# Encoder.net
KiCad netlist of a schematic drawn in Altium Designer
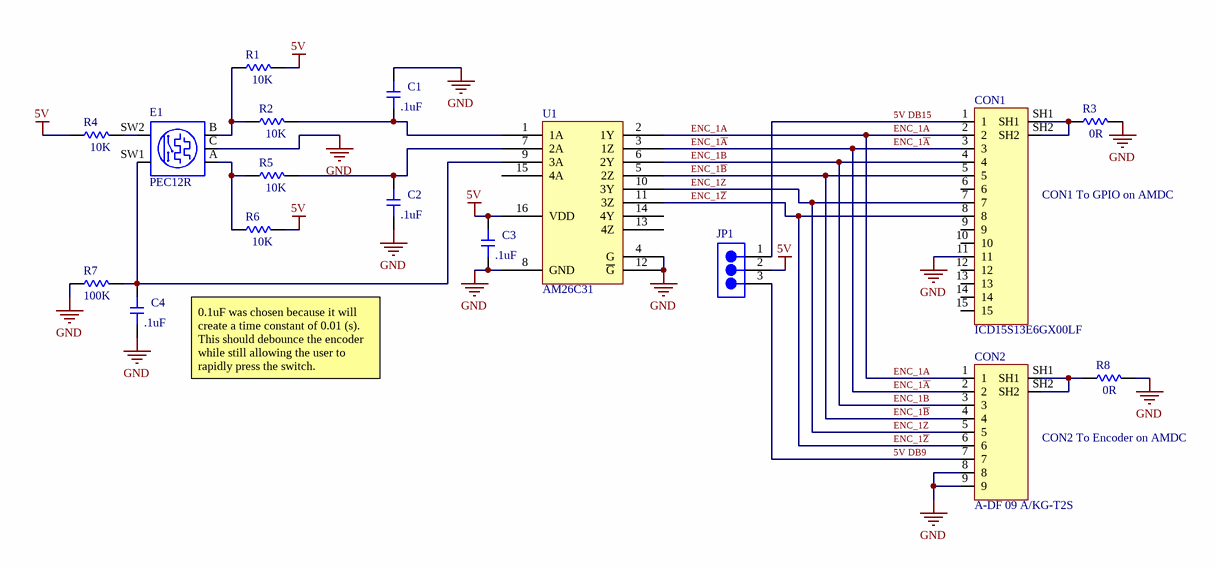
[diagram p0: Encoder.SchDoc]

(export (version "E")
  (design (tool "Eeschema 10.0.6"))
  (components
    (comp (ref "C1")
      (value "Capacitor .1uF")
      (footprint ".1uF Capacitor (0603-CAP)")
      (description "Capacitor")
      (libsource (lib "Encoder") (part "Capacitor .1uF"))
    )
    (comp (ref "C2")
      (value "Capacitor .1uF")
      (footprint ".1uF Capacitor (0603-CAP)")
      (description "Capacitor")
      (libsource (lib "Encoder") (part "Capacitor .1uF"))
    )
    (comp (ref "C3")
      (value "Capacitor .1uF")
      (footprint ".1uF Capacitor (0603-CAP)")
      (description "Capacitor")
      (libsource (lib "Encoder") (part "Capacitor .1uF"))
    )
    (comp (ref "C4")
      (value "Capacitor .1uF")
      (footprint ".1uF Capacitor (0603-CAP)")
      (description "Capacitor")
      (libsource (lib "Encoder") (part "Capacitor .1uF"))
    )
    (comp (ref "CON1")
      (value "ICD15S13E6GX00LF")
      (footprint "ICD15S")
      (description "CONN D-SUB PLUG 15POS R/A SLDR")
      (libsource (lib "Encoder") (part "ICD15S13E6GX00LF"))
    )
    (comp (ref "CON2")
      (value "A-DF 09 A/KG-T2S")
      (footprint "DB9 Connector")
      (description "9 Position D-Sub Receptacle, Female Sockets Connector")
      (fields (field (name "MF") "Assmann WSW"))
      (libsource (lib "Encoder") (part "DB9 Connector A-DF_09_A/KG-T2S"))
    )
    (comp (ref "E1")
      (value "PEC12R")
      (footprint "Encoder")
      (libsource (lib "Encoder") (part "PEC12R-4220F-S0024"))
    )
    (comp (ref "JP1")
      (value "Jumper3")
      (footprint "PIN_HEADER_1X3")
      (libsource (lib "Encoder") (part "Jumper3"))
    )
    (comp (ref "R1")
      (value "Resistor")
      (footprint "10K Resistor (0603-RES)")
      (libsource (lib "Encoder") (part "Resistor 10K"))
    )
    (comp (ref "R2")
      (value "Resistor")
      (footprint "10K Resistor (0603-RES)")
      (libsource (lib "Encoder") (part "Resistor 10K"))
    )
    (comp (ref "R3")
      (value "Resistor")
      (footprint "0 Resistor (1206-RES)")
      (libsource (lib "Encoder") (part "Resistor 0R"))
    )
    (comp (ref "R4")
      (value "Resistor")
      (footprint "10K Resistor (0603-RES)")
      (libsource (lib "Encoder") (part "Resistor 10K"))
    )
    (comp (ref "R5")
      (value "Resistor")
      (footprint "10K Resistor (0603-RES)")
      (libsource (lib "Encoder") (part "Resistor 10K"))
    )
    (comp (ref "R6")
      (value "Resistor")
      (footprint "10K Resistor (0603-RES)")
      (libsource (lib "Encoder") (part "Resistor 10K"))
    )
    (comp (ref "R7")
      (value "Resistor")
      (footprint "100K Resistor (0603-RES)")
      (libsource (lib "Encoder") (part "Resistor 100K"))
    )
    (comp (ref "R8")
      (value "Resistor")
      (footprint "0 Resistor (1206-RES)")
      (libsource (lib "Encoder") (part "Resistor 0R"))
    )
    (comp (ref "U1")
      (value "AM26C31")
      (footprint "AM26C31")
      (description "IC DRIVER 4/0 16TSSOP")
      (libsource (lib "Encoder") (part "AM26C31"))
    )
  )
  (nets
    (net (code "1") (name "/5V DB9") (class "Default")
      (node (ref "CON2") (pin "7") (pinfunction "7_7") (pintype "passive"))
      (node (ref "JP1") (pin "3") (pinfunction "75_3") (pintype "passive"))
    )
    (net (code "2") (name "/5V DB15") (class "Default")
      (node (ref "CON1") (pin "1") (pinfunction "1_1") (pintype "passive"))
      (node (ref "JP1") (pin "1") (pinfunction "76_1") (pintype "passive"))
    )
    (net (code "3") (name "/ENC_1A") (class "Default")
      (node (ref "CON1") (pin "2") (pinfunction "2_2") (pintype "passive"))
      (node (ref "CON2") (pin "1") (pinfunction "1_1") (pintype "passive"))
      (node (ref "U1") (pin "2") (pinfunction "1Y_2") (pintype "passive"))
    )
    (net (code "4") (name "/ENC_1B") (class "Default")
      (node (ref "CON1") (pin "4") (pinfunction "4_4") (pintype "passive"))
      (node (ref "CON2") (pin "3") (pinfunction "3_3") (pintype "passive"))
      (node (ref "U1") (pin "6") (pinfunction "2Y_6") (pintype "passive"))
    )
    (net (code "5") (name "/ENC_1Z") (class "Default")
      (node (ref "CON1") (pin "7") (pinfunction "7_7") (pintype "passive"))
      (node (ref "CON2") (pin "5") (pinfunction "5_5") (pintype "passive"))
      (node (ref "U1") (pin "10") (pinfunction "3Y_10") (pintype "passive"))
    )
    (net (code "6") (name "/ENC_1~{A}") (class "Default")
      (node (ref "CON1") (pin "3") (pinfunction "3_3") (pintype "passive"))
      (node (ref "CON2") (pin "2") (pinfunction "2_2") (pintype "passive"))
      (node (ref "U1") (pin "3") (pinfunction "1Z_3") (pintype "passive"))
    )
    (net (code "7") (name "/ENC_1~{B}") (class "Default")
      (node (ref "CON1") (pin "5") (pinfunction "5_5") (pintype "passive"))
      (node (ref "CON2") (pin "4") (pinfunction "4_4") (pintype "passive"))
      (node (ref "U1") (pin "5") (pinfunction "2Z_5") (pintype "passive"))
    )
    (net (code "8") (name "/ENC_1~{Z}") (class "Default")
      (node (ref "CON1") (pin "8") (pinfunction "8_8") (pintype "passive"))
      (node (ref "CON2") (pin "6") (pinfunction "6_6") (pintype "passive"))
      (node (ref "U1") (pin "11") (pinfunction "3Z_11") (pintype "passive"))
    )
    (net (code "9") (name "5V") (class "Default")
      (node (ref "C3") (pin "1") (pinfunction "1_1") (pintype "passive"))
      (node (ref "JP1") (pin "2") (pinfunction "75_2") (pintype "passive"))
      (node (ref "R1") (pin "2") (pinfunction "2_2") (pintype "passive"))
      (node (ref "R4") (pin "1") (pinfunction "1_1") (pintype "passive"))
      (node (ref "R6") (pin "2") (pinfunction "2_2") (pintype "passive"))
      (node (ref "U1") (pin "16") (pinfunction "VDD_16") (pintype "passive"))
    )
    (net (code "10") (name "GND") (class "Default")
      (node (ref "C1") (pin "1") (pinfunction "1_1") (pintype "passive"))
      (node (ref "C2") (pin "2") (pinfunction "2_2") (pintype "passive"))
      (node (ref "C3") (pin "2") (pinfunction "2_2") (pintype "passive"))
      (node (ref "C4") (pin "2") (pinfunction "2_2") (pintype "passive"))
      (node (ref "CON1") (pin "11") (pinfunction "11_11") (pintype "passive"))
      (node (ref "CON2") (pin "8") (pinfunction "8_8") (pintype "passive"))
      (node (ref "CON2") (pin "9") (pinfunction "9_9") (pintype "passive"))
      (node (ref "E1") (pin "C") (pinfunction "C_C") (pintype "passive"))
      (node (ref "R3") (pin "2") (pinfunction "2_2") (pintype "passive"))
      (node (ref "R7") (pin "1") (pinfunction "1_1") (pintype "passive"))
      (node (ref "R8") (pin "2") (pinfunction "2_2") (pintype "passive"))
      (node (ref "U1") (pin "12") (pinfunction "~{G}_12") (pintype "passive"))
      (node (ref "U1") (pin "4") (pinfunction "G_4") (pintype "passive"))
      (node (ref "U1") (pin "8") (pinfunction "GND_8") (pintype "passive"))
    )
    (net (code "11") (name "Net-(CON1-PadSH1)") (class "Default")
      (node (ref "CON1") (pin "SH1") (pinfunction "SH1_SH1") (pintype "passive"))
      (node (ref "CON1") (pin "SH2") (pinfunction "SH2_SH2") (pintype "passive"))
      (node (ref "R3") (pin "1") (pinfunction "1_1") (pintype "passive"))
    )
    (net (code "12") (name "Net-(CON2-PadSH1)") (class "Default")
      (node (ref "CON2") (pin "SH1") (pinfunction "SH1_SH1") (pintype "passive"))
      (node (ref "CON2") (pin "SH2") (pinfunction "SH2_SH2") (pintype "passive"))
      (node (ref "R8") (pin "1") (pinfunction "1_1") (pintype "passive"))
    )
    (net (code "13") (name "Net-(E1-PadA)") (class "Default")
      (node (ref "E1") (pin "A") (pinfunction "A_A") (pintype "passive"))
      (node (ref "R5") (pin "1") (pinfunction "1_1") (pintype "passive"))
      (node (ref "R6") (pin "1") (pinfunction "1_1") (pintype "passive"))
    )
    (net (code "14") (name "Net-(E1-PadB)") (class "Default")
      (node (ref "E1") (pin "B") (pinfunction "B_B") (pintype "passive"))
      (node (ref "R1") (pin "1") (pinfunction "1_1") (pintype "passive"))
      (node (ref "R2") (pin "1") (pinfunction "1_1") (pintype "passive"))
    )
    (net (code "15") (name "Net-(E1-PadSW2)") (class "Default")
      (node (ref "E1") (pin "SW2") (pinfunction "SW2_SW2") (pintype "passive"))
      (node (ref "R4") (pin "2") (pinfunction "2_2") (pintype "passive"))
    )
    (net (code "16") (name "Net-(U1-1A)") (class "Default")
      (node (ref "C1") (pin "2") (pinfunction "2_2") (pintype "passive"))
      (node (ref "R2") (pin "2") (pinfunction "2_2") (pintype "passive"))
      (node (ref "U1") (pin "1") (pinfunction "1A_1") (pintype "passive"))
    )
    (net (code "17") (name "Net-(U1-2A)") (class "Default")
      (node (ref "C2") (pin "1") (pinfunction "1_1") (pintype "passive"))
      (node (ref "R5") (pin "2") (pinfunction "2_2") (pintype "passive"))
      (node (ref "U1") (pin "7") (pinfunction "2A_7") (pintype "passive"))
    )
    (net (code "18") (name "Net-(U1-3A)") (class "Default")
      (node (ref "C4") (pin "1") (pinfunction "1_1") (pintype "passive"))
      (node (ref "E1") (pin "SW1") (pinfunction "SW1_SW1") (pintype "passive"))
      (node (ref "R7") (pin "2") (pinfunction "2_2") (pintype "passive"))
      (node (ref "U1") (pin "9") (pinfunction "3A_9") (pintype "passive"))
    )
    (net (code "19") (name "unconnected-(CON1-Pad6)") (class "Default")
      (node (ref "CON1") (pin "6") (pinfunction "6_6") (pintype "passive"))
    )
    (net (code "20") (name "unconnected-(CON1-Pad9)") (class "Default")
      (node (ref "CON1") (pin "9") (pinfunction "9_9") (pintype "passive"))
    )
    (net (code "21") (name "unconnected-(CON1-Pad10)") (class "Default")
      (node (ref "CON1") (pin "10") (pinfunction "10_10") (pintype "passive"))
    )
    (net (code "22") (name "unconnected-(CON1-Pad12)") (class "Default")
      (node (ref "CON1") (pin "12") (pinfunction "12_12") (pintype "passive"))
    )
    (net (code "23") (name "unconnected-(CON1-Pad13)") (class "Default")
      (node (ref "CON1") (pin "13") (pinfunction "13_13") (pintype "passive"))
    )
    (net (code "24") (name "unconnected-(CON1-Pad14)") (class "Default")
      (node (ref "CON1") (pin "14") (pinfunction "14_14") (pintype "passive"))
    )
    (net (code "25") (name "unconnected-(CON1-Pad15)") (class "Default")
      (node (ref "CON1") (pin "15") (pinfunction "15_15") (pintype "passive"))
    )
    (net (code "26") (name "unconnected-(U1-4A-Pad15)") (class "Default")
      (node (ref "U1") (pin "15") (pinfunction "4A_15") (pintype "passive"))
    )
    (net (code "27") (name "unconnected-(U1-4Y-Pad14)") (class "Default")
      (node (ref "U1") (pin "14") (pinfunction "4Y_14") (pintype "passive"))
    )
    (net (code "28") (name "unconnected-(U1-4Z-Pad13)") (class "Default")
      (node (ref "U1") (pin "13") (pinfunction "4Z_13") (pintype "passive"))
    )
  )
)
